# TherrmistorMux.net
KiCad netlist of a schematic drawn in Altium Designer
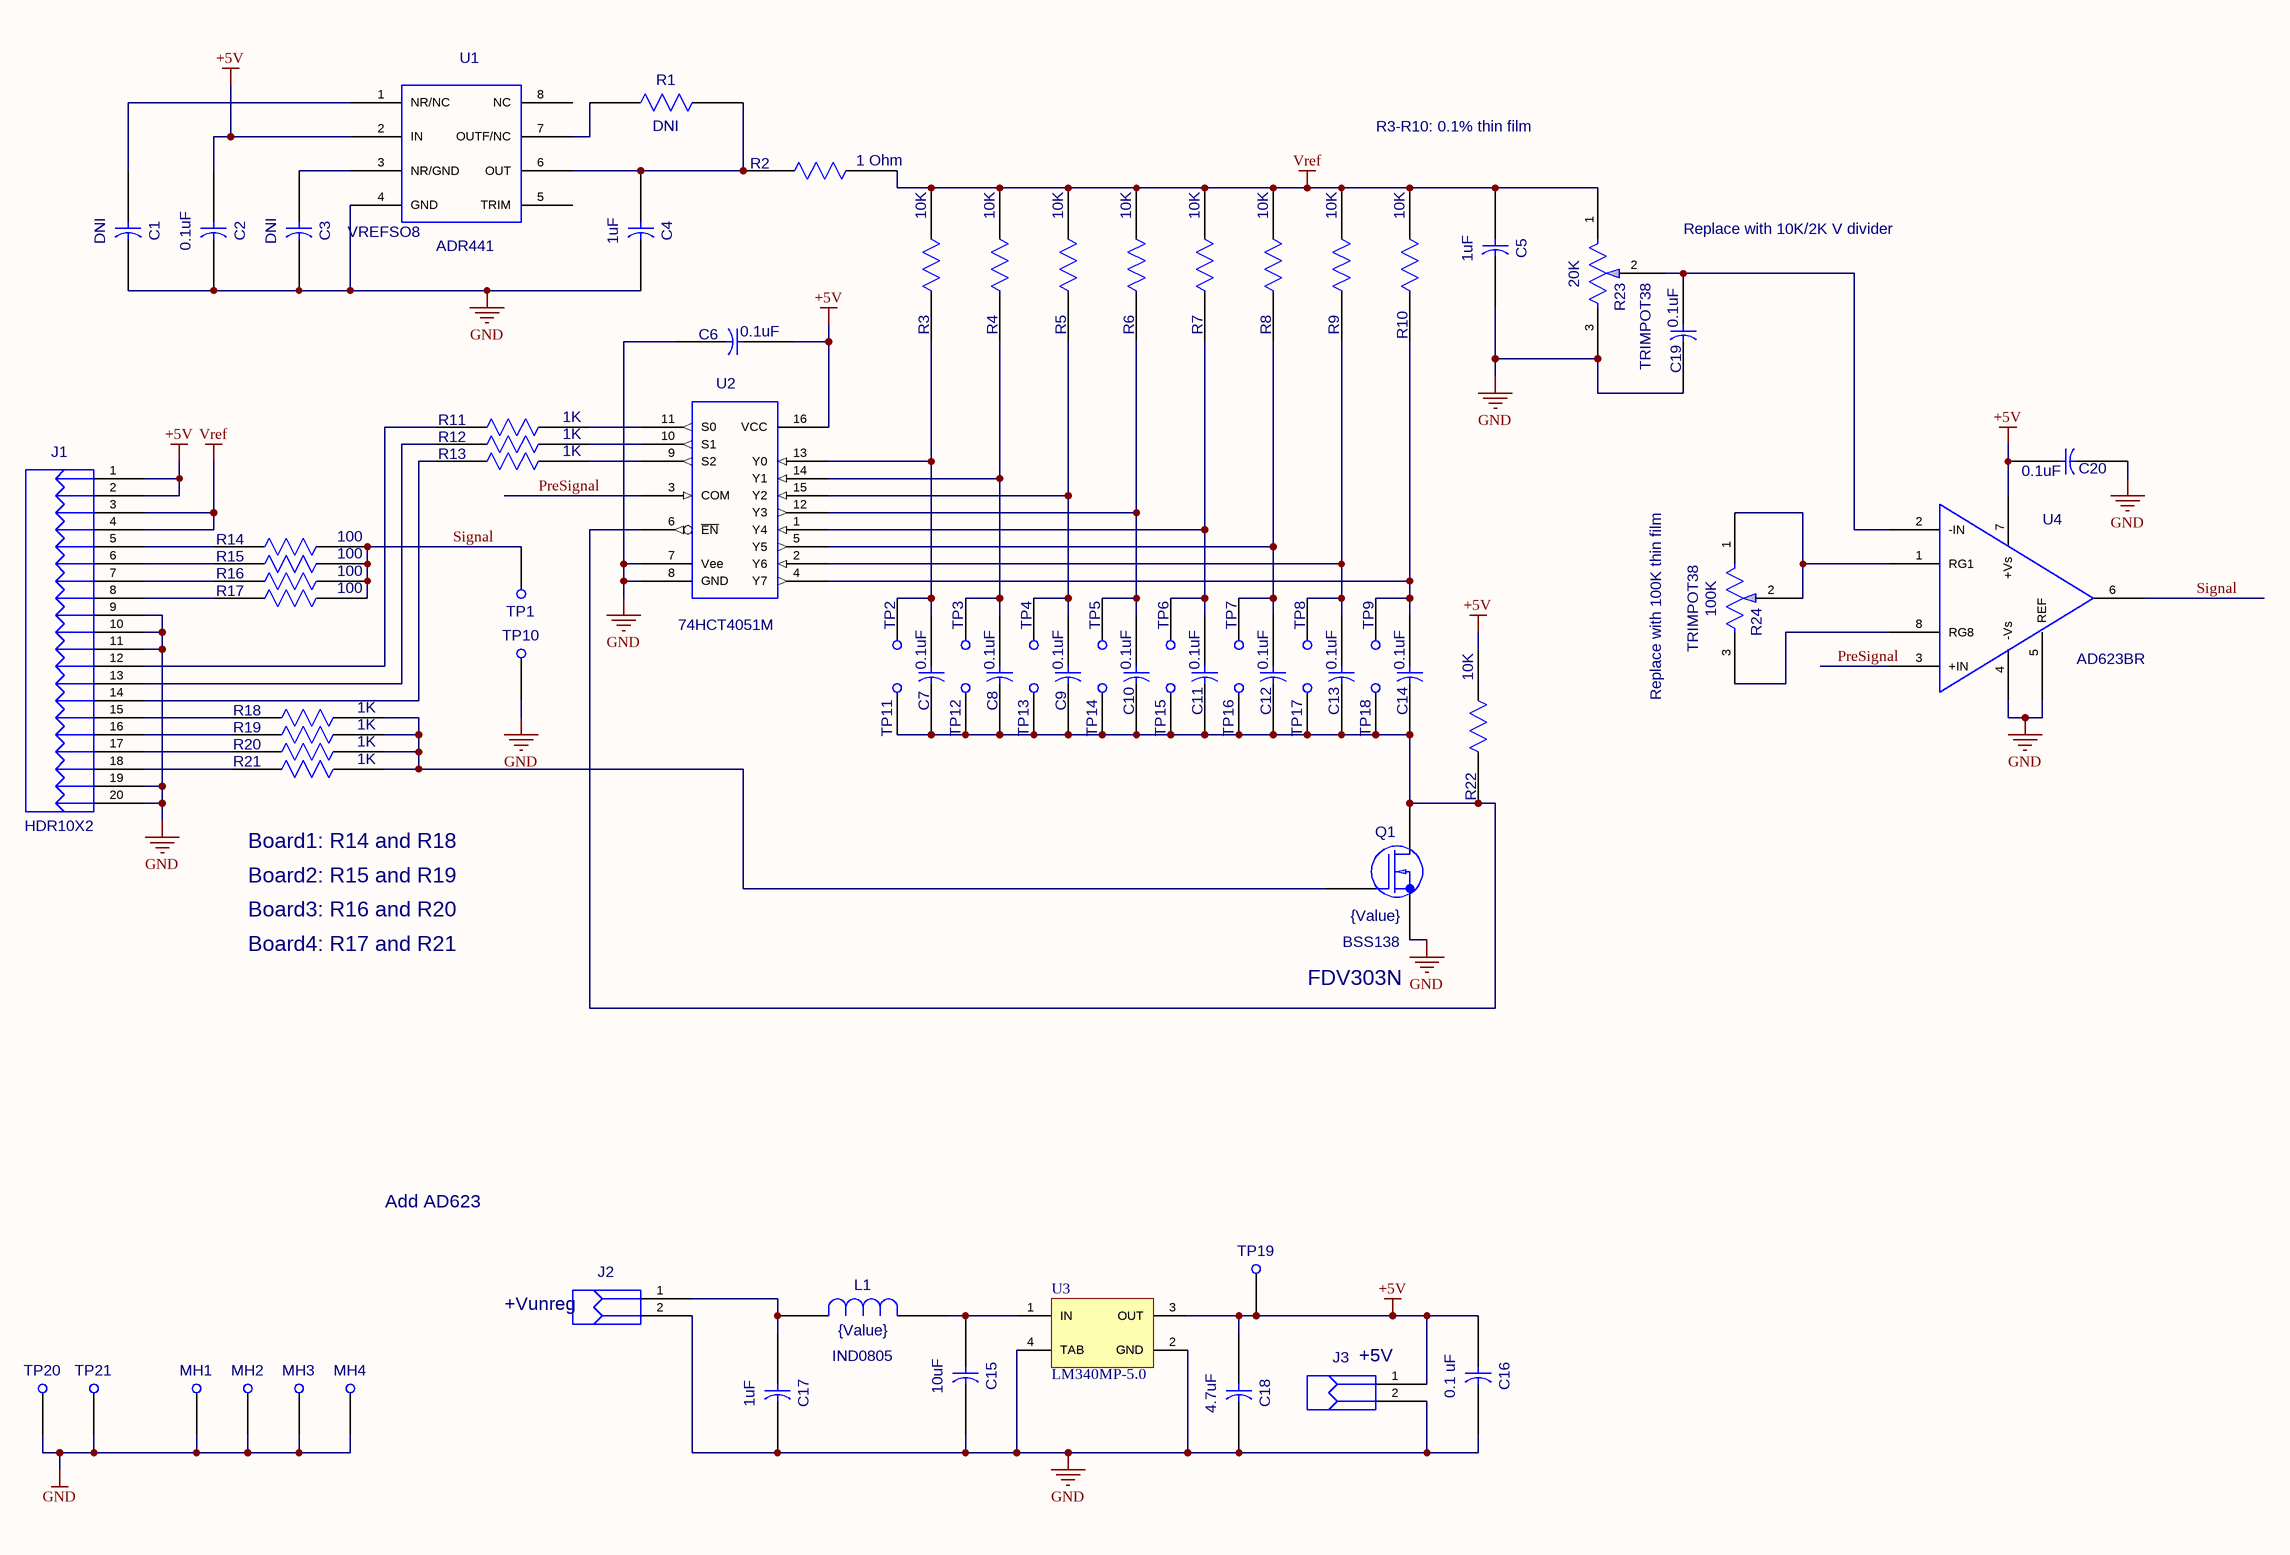
[diagram p0: TherrmistorMux.SchDoc]

(export (version "E")
  (design (tool "Eeschema 10.0.6"))
  (components
    (comp (ref "C1")
      (value "DNI")
      (footprint "RC0603")
      (description "CAP0603")
      (libsource (lib "JMAC") (part "CAP0603"))
    )
    (comp (ref "C2")
      (value "0.1uF")
      (footprint "RC0603")
      (description "CAP0603")
      (libsource (lib "JMAC") (part "CAP0603"))
    )
    (comp (ref "C3")
      (value "DNI")
      (footprint "RC0603")
      (description "CAP0603")
      (libsource (lib "JMAC") (part "CAP0603"))
    )
    (comp (ref "C4")
      (value "1uF")
      (footprint "RC0805_CAP0805(Primary)")
      (description "CAP0805")
      (libsource (lib "JMAC") (part "CAP0805"))
    )
    (comp (ref "C5")
      (value "1uF")
      (footprint "RC0805_CAP0805(Primary)")
      (description "CAP0805")
      (libsource (lib "JMAC") (part "CAP0805"))
    )
    (comp (ref "C6")
      (value "0.1uF")
      (footprint "RC0603")
      (description "CAP0603")
      (libsource (lib "JMAC") (part "CAP0603"))
    )
    (comp (ref "C7")
      (value "0.1uF")
      (footprint "RC0805_CAP0805(Primary)")
      (description "CAP0805")
      (libsource (lib "JMAC") (part "CAP0805"))
    )
    (comp (ref "C8")
      (value "0.1uF")
      (footprint "RC0805_CAP0805(Primary)")
      (description "CAP0805")
      (libsource (lib "JMAC") (part "CAP0805"))
    )
    (comp (ref "C9")
      (value "0.1uF")
      (footprint "RC0805_CAP0805(Primary)")
      (description "CAP0805")
      (libsource (lib "JMAC") (part "CAP0805"))
    )
    (comp (ref "C10")
      (value "0.1uF")
      (footprint "RC0805_CAP0805(Primary)")
      (description "CAP0805")
      (libsource (lib "JMAC") (part "CAP0805"))
    )
    (comp (ref "C11")
      (value "0.1uF")
      (footprint "RC0805_CAP0805(Primary)")
      (description "CAP0805")
      (libsource (lib "JMAC") (part "CAP0805"))
    )
    (comp (ref "C12")
      (value "0.1uF")
      (footprint "RC0805_CAP0805(Primary)")
      (description "CAP0805")
      (libsource (lib "JMAC") (part "CAP0805"))
    )
    (comp (ref "C13")
      (value "0.1uF")
      (footprint "RC0805_CAP0805(Primary)")
      (description "CAP0805")
      (libsource (lib "JMAC") (part "CAP0805"))
    )
    (comp (ref "C14")
      (value "0.1uF")
      (footprint "RC0805_CAP0805(Primary)")
      (description "CAP0805")
      (libsource (lib "JMAC") (part "CAP0805"))
    )
    (comp (ref "C15")
      (value "10uF")
      (footprint "RC1206_CAP1206(Primary)")
      (description "CAP1206")
      (libsource (lib "JMAC") (part "CAP1206"))
    )
    (comp (ref "C16")
      (value "0.1 uF")
      (footprint "RC0805_CAP0805(Primary)")
      (description "CAP0805")
      (libsource (lib "JMAC") (part "CAP0805"))
    )
    (comp (ref "C17")
      (value "1uF")
      (footprint "RC1206_CAP1206(Primary)")
      (description "CAP1206")
      (libsource (lib "JMAC") (part "CAP1206"))
    )
    (comp (ref "C18")
      (value "4.7uF")
      (footprint "RC1206_CAP1206(Primary)")
      (description "CAP1206")
      (libsource (lib "JMAC") (part "CAP1206"))
    )
    (comp (ref "C19")
      (value "0.1uF")
      (footprint "RC0603")
      (description "CAP0603")
      (libsource (lib "JMAC") (part "CAP0603"))
    )
    (comp (ref "C20")
      (value "0.1uF")
      (footprint "RC0603")
      (description "CAP0603")
      (libsource (lib "JMAC") (part "CAP0603"))
    )
    (comp (ref "J1") (value "HDR10X2") (footprint "HDR10X2") (libsource (lib "JMAC") (part "HDR10X2")))
    (comp (ref "J2")
      (value "CONN2P35MM")
      (footprint "CONN2P35MM")
      (libsource (lib "JMAC") (part "CONN2P35MM"))
    )
    (comp (ref "J3")
      (value "CONN2P35MM")
      (footprint "CONN2P35MM")
      (libsource (lib "JMAC") (part "CONN2P35MM"))
    )
    (comp (ref "L1")
      (value "IND0805")
      (footprint "RC0805_IND0805(Primary)")
      (fields (field (name "ALTIUM_VALUE") "{Value}"))
      (libsource (lib "JMAC") (part "IND0805"))
    )
    (comp (ref "MH1") (value "MH440") (footprint "M440_MH440()") (libsource (lib "*") (part "MH440")))
    (comp (ref "MH2") (value "MH440") (footprint "M440_MH440()") (libsource (lib "*") (part "MH440")))
    (comp (ref "MH3") (value "MH440") (footprint "M440_MH440()") (libsource (lib "*") (part "MH440")))
    (comp (ref "MH4") (value "MH440") (footprint "M440_MH440()") (libsource (lib "*") (part "MH440")))
    (comp (ref "Q1")
      (value "BSS138")
      (footprint "SOT-23")
      (fields (field (name "ALTIUM_VALUE") "{Value}"))
      (libsource (lib "JMAC") (part "BSS138"))
    )
    (comp (ref "R1")
      (value "DNI")
      (footprint "RC0603")
      (description "RES0603")
      (libsource (lib "JMAC") (part "RES0603"))
    )
    (comp (ref "R2")
      (value "1 Ohm")
      (footprint "RC0805_RES0805(Primary)")
      (description "RES0805")
      (libsource (lib "JMAC") (part "RES0805"))
    )
    (comp (ref "R3")
      (value "10K")
      (footprint "RC0805_RES0805(Primary)")
      (description "RES0805")
      (libsource (lib "JMAC") (part "RES0805"))
    )
    (comp (ref "R4")
      (value "10K")
      (footprint "RC0805_RES0805(Primary)")
      (description "RES0805")
      (libsource (lib "JMAC") (part "RES0805"))
    )
    (comp (ref "R5")
      (value "10K")
      (footprint "RC0805_RES0805(Primary)")
      (description "RES0805")
      (libsource (lib "JMAC") (part "RES0805"))
    )
    (comp (ref "R6")
      (value "10K")
      (footprint "RC0805_RES0805(Primary)")
      (description "RES0805")
      (libsource (lib "JMAC") (part "RES0805"))
    )
    (comp (ref "R7")
      (value "10K")
      (footprint "RC0805_RES0805(Primary)")
      (description "RES0805")
      (libsource (lib "JMAC") (part "RES0805"))
    )
    (comp (ref "R8")
      (value "10K")
      (footprint "RC0805_RES0805(Primary)")
      (description "RES0805")
      (libsource (lib "JMAC") (part "RES0805"))
    )
    (comp (ref "R9")
      (value "10K")
      (footprint "RC0805_RES0805(Primary)")
      (description "RES0805")
      (libsource (lib "JMAC") (part "RES0805"))
    )
    (comp (ref "R10")
      (value "10K")
      (footprint "RC0805_RES0805(Primary)")
      (description "RES0805")
      (libsource (lib "JMAC") (part "RES0805"))
    )
    (comp (ref "R11")
      (value "1K")
      (footprint "RC0805_RES0805(Primary)")
      (description "RES0805")
      (libsource (lib "JMAC") (part "RES0805"))
    )
    (comp (ref "R12")
      (value "1K")
      (footprint "RC0805_RES0805(Primary)")
      (description "RES0805")
      (libsource (lib "JMAC") (part "RES0805"))
    )
    (comp (ref "R13")
      (value "1K")
      (footprint "RC0805_RES0805(Primary)")
      (description "RES0805")
      (libsource (lib "JMAC") (part "RES0805"))
    )
    (comp (ref "R14")
      (value "100")
      (footprint "RC0805_RES0805(Primary)")
      (description "RES0805")
      (libsource (lib "JMAC") (part "RES0805"))
    )
    (comp (ref "R15")
      (value "100")
      (footprint "RC0805_RES0805(Primary)")
      (description "RES0805")
      (libsource (lib "JMAC") (part "RES0805"))
    )
    (comp (ref "R16")
      (value "100")
      (footprint "RC0805_RES0805(Primary)")
      (description "RES0805")
      (libsource (lib "JMAC") (part "RES0805"))
    )
    (comp (ref "R17")
      (value "100")
      (footprint "RC0805_RES0805(Primary)")
      (description "RES0805")
      (libsource (lib "JMAC") (part "RES0805"))
    )
    (comp (ref "R18")
      (value "1K")
      (footprint "RC0805_RES0805(Primary)")
      (description "RES0805")
      (libsource (lib "JMAC") (part "RES0805"))
    )
    (comp (ref "R19")
      (value "1K")
      (footprint "RC0805_RES0805(Primary)")
      (description "RES0805")
      (libsource (lib "JMAC") (part "RES0805"))
    )
    (comp (ref "R20")
      (value "1K")
      (footprint "RC0805_RES0805(Primary)")
      (description "RES0805")
      (libsource (lib "JMAC") (part "RES0805"))
    )
    (comp (ref "R21")
      (value "1K")
      (footprint "RC0805_RES0805(Primary)")
      (description "RES0805")
      (libsource (lib "JMAC") (part "RES0805"))
    )
    (comp (ref "R22")
      (value "10K")
      (footprint "RC0805_RES0805(Primary)")
      (description "RES0805")
      (libsource (lib "JMAC") (part "RES0805"))
    )
    (comp (ref "R23")
      (value "TRIMPOT38")
      (footprint "TRIM38")
      (fields (field (name "ALTIUM_VALUE") "20K"))
      (libsource (lib "JMAC") (part "TRIMPOT38"))
    )
    (comp (ref "R24")
      (value "TRIMPOT38")
      (footprint "TRIM38")
      (fields (field (name "ALTIUM_VALUE") "100K"))
      (libsource (lib "JMAC") (part "TRIMPOT38"))
    )
    (comp (ref "TP1") (value "TP38") (footprint "TP38") (libsource (lib "JMAC") (part "TP38")))
    (comp (ref "TP2") (value "TP24") (footprint "TP24") (libsource (lib "JMAC") (part "TP24")))
    (comp (ref "TP3") (value "TP24") (footprint "TP24") (libsource (lib "JMAC") (part "TP24")))
    (comp (ref "TP4") (value "TP24") (footprint "TP24") (libsource (lib "JMAC") (part "TP24")))
    (comp (ref "TP5") (value "TP24") (footprint "TP24") (libsource (lib "JMAC") (part "TP24")))
    (comp (ref "TP6") (value "TP24") (footprint "TP24") (libsource (lib "JMAC") (part "TP24")))
    (comp (ref "TP7") (value "TP24") (footprint "TP24") (libsource (lib "JMAC") (part "TP24")))
    (comp (ref "TP8") (value "TP24") (footprint "TP24") (libsource (lib "JMAC") (part "TP24")))
    (comp (ref "TP9") (value "TP24") (footprint "TP24") (libsource (lib "JMAC") (part "TP24")))
    (comp (ref "TP10") (value "TP38") (footprint "TP38") (libsource (lib "JMAC") (part "TP38")))
    (comp (ref "TP11") (value "TP24") (footprint "TP24") (libsource (lib "JMAC") (part "TP24")))
    (comp (ref "TP12") (value "TP24") (footprint "TP24") (libsource (lib "JMAC") (part "TP24")))
    (comp (ref "TP13") (value "TP24") (footprint "TP24") (libsource (lib "JMAC") (part "TP24")))
    (comp (ref "TP14") (value "TP24") (footprint "TP24") (libsource (lib "JMAC") (part "TP24")))
    (comp (ref "TP15") (value "TP24") (footprint "TP24") (libsource (lib "JMAC") (part "TP24")))
    (comp (ref "TP16") (value "TP24") (footprint "TP24") (libsource (lib "JMAC") (part "TP24")))
    (comp (ref "TP17") (value "TP24") (footprint "TP24") (libsource (lib "JMAC") (part "TP24")))
    (comp (ref "TP18") (value "TP24") (footprint "TP24") (libsource (lib "JMAC") (part "TP24")))
    (comp (ref "TP19") (value "TP52") (footprint "TP52") (libsource (lib "JMAC") (part "TP52")))
    (comp (ref "TP20") (value "TP52") (footprint "TP52") (libsource (lib "JMAC") (part "TP52")))
    (comp (ref "TP21") (value "TP52") (footprint "TP52") (libsource (lib "JMAC") (part "TP52")))
    (comp (ref "U1")
      (value "VREFSO8")
      (footprint "SO8")
      (fields (field (name "ALTIUM_VALUE") "ADR441"))
      (libsource (lib "JMAC") (part "VREFSO8"))
    )
    (comp (ref "U2") (value "74HCT4051M") (footprint "SO16") (libsource (lib "JMAC") (part "74HCT4051M")))
    (comp (ref "U3")
      (value "LM340MP-5.0")
      (footprint "MP04A_N")
      (description "Series 3-Terminal Positive Regulators")
      (fields
        (field (name "MANUFACTURER") "National Semiconductor")
        (field (name "DIGIKEYPARTNUMBER") "LM340MP-5.0CT-ND")
        (field (name "PUBLISHER") "Altium Limited")
      )
      (libsource (lib "NSC LDO") (part "LM340MP-5.0"))
    )
    (comp (ref "U4")
      (value "AD623BR")
      (footprint "SO8")
      (description "AD620BR")
      (libsource (lib "JMAC") (part "AD620BR"))
    )
  )
  (nets
    (net (code "1") (name "+5V") (class "Default")
      (node (ref "C16") (pin "A") (pinfunction "A_A") (pintype "passive"))
      (node (ref "C18") (pin "A") (pinfunction "A_A") (pintype "passive"))
      (node (ref "C2") (pin "2") (pintype "passive"))
      (node (ref "C20") (pin "2") (pintype "passive"))
      (node (ref "C6") (pin "2") (pintype "passive"))
      (node (ref "J1") (pin "1") (pinfunction "P1_1") (pintype "passive"))
      (node (ref "J1") (pin "2") (pinfunction "P2_2") (pintype "passive"))
      (node (ref "J3") (pin "1") (pintype "passive"))
      (node (ref "R22") (pin "B") (pinfunction "B_B") (pintype "passive"))
      (node (ref "TP19") (pin "1") (pintype "passive"))
      (node (ref "U1") (pin "2") (pinfunction "IN_2") (pintype "passive"))
      (node (ref "U2") (pin "16") (pinfunction "VCC_16") (pintype "power_in"))
      (node (ref "U3") (pin "3") (pinfunction "OUT_3") (pintype "power_in"))
      (node (ref "U4") (pin "7") (pinfunction "+Vs_7") (pintype "passive"))
    )
    (net (code "2") (name "/PreSignal") (class "Default")
      (node (ref "U2") (pin "3") (pinfunction "COM_3") (pintype "input"))
      (node (ref "U4") (pin "3") (pinfunction "+IN_3") (pintype "passive"))
    )
    (net (code "3") (name "/Signal") (class "Default")
      (node (ref "R14") (pin "B") (pinfunction "B_B") (pintype "passive"))
      (node (ref "R15") (pin "B") (pinfunction "B_B") (pintype "passive"))
      (node (ref "R16") (pin "B") (pinfunction "B_B") (pintype "passive"))
      (node (ref "R17") (pin "B") (pinfunction "B_B") (pintype "passive"))
      (node (ref "TP1") (pin "1") (pintype "passive"))
      (node (ref "U4") (pin "6") (pinfunction "OUT_6") (pintype "passive"))
    )
    (net (code "4") (name "GND") (class "Default")
      (node (ref "C1") (pin "1") (pintype "passive"))
      (node (ref "C15") (pin "B") (pinfunction "B_B") (pintype "passive"))
      (node (ref "C16") (pin "B") (pinfunction "B_B") (pintype "passive"))
      (node (ref "C17") (pin "B") (pinfunction "B_B") (pintype "passive"))
      (node (ref "C18") (pin "B") (pinfunction "B_B") (pintype "passive"))
      (node (ref "C19") (pin "1") (pintype "passive"))
      (node (ref "C2") (pin "1") (pintype "passive"))
      (node (ref "C20") (pin "1") (pintype "passive"))
      (node (ref "C3") (pin "1") (pintype "passive"))
      (node (ref "C4") (pin "B") (pinfunction "B_B") (pintype "passive"))
      (node (ref "C5") (pin "B") (pinfunction "B_B") (pintype "passive"))
      (node (ref "C6") (pin "1") (pintype "passive"))
      (node (ref "J1") (pin "10") (pinfunction "P10_10") (pintype "passive"))
      (node (ref "J1") (pin "11") (pinfunction "P11_11") (pintype "passive"))
      (node (ref "J1") (pin "19") (pinfunction "P19_19") (pintype "passive"))
      (node (ref "J1") (pin "20") (pinfunction "P20_20") (pintype "passive"))
      (node (ref "J1") (pin "9") (pinfunction "P9_9") (pintype "passive"))
      (node (ref "J2") (pin "2") (pintype "passive"))
      (node (ref "J3") (pin "2") (pintype "passive"))
      (node (ref "MH1") (pin "1") (pintype "passive"))
      (node (ref "MH2") (pin "1") (pintype "passive"))
      (node (ref "MH3") (pin "1") (pintype "passive"))
      (node (ref "MH4") (pin "1") (pintype "passive"))
      (node (ref "Q1") (pin "2") (pinfunction "S_2") (pintype "passive"))
      (node (ref "R23") (pin "3") (pintype "passive"))
      (node (ref "TP10") (pin "1") (pintype "passive"))
      (node (ref "TP20") (pin "1") (pintype "passive"))
      (node (ref "TP21") (pin "1") (pintype "passive"))
      (node (ref "U1") (pin "4") (pinfunction "GND_4") (pintype "passive"))
      (node (ref "U2") (pin "7") (pinfunction "Vee_7") (pintype "power_in"))
      (node (ref "U2") (pin "8") (pinfunction "GND_8") (pintype "power_in"))
      (node (ref "U3") (pin "2") (pinfunction "GND_2") (pintype "power_in"))
      (node (ref "U3") (pin "4") (pinfunction "TAB_4") (pintype "power_in"))
      (node (ref "U4") (pin "4") (pinfunction "-Vs_4") (pintype "passive"))
      (node (ref "U4") (pin "5") (pinfunction "REF_5") (pintype "passive"))
    )
    (net (code "5") (name "Net-(C17-PadA)") (class "Default")
      (node (ref "C17") (pin "A") (pinfunction "A_A") (pintype "passive"))
      (node (ref "J2") (pin "1") (pintype "passive"))
      (node (ref "L1") (pin "B") (pinfunction "B_B") (pintype "passive"))
    )
    (net (code "6") (name "Net-(J1-P5)") (class "Default")
      (node (ref "J1") (pin "5") (pinfunction "P5_5") (pintype "passive"))
      (node (ref "R14") (pin "A") (pinfunction "A_A") (pintype "passive"))
    )
    (net (code "7") (name "Net-(J1-P6)") (class "Default")
      (node (ref "J1") (pin "6") (pinfunction "P6_6") (pintype "passive"))
      (node (ref "R15") (pin "A") (pinfunction "A_A") (pintype "passive"))
    )
    (net (code "8") (name "Net-(J1-P7)") (class "Default")
      (node (ref "J1") (pin "7") (pinfunction "P7_7") (pintype "passive"))
      (node (ref "R16") (pin "A") (pinfunction "A_A") (pintype "passive"))
    )
    (net (code "9") (name "Net-(J1-P8)") (class "Default")
      (node (ref "J1") (pin "8") (pinfunction "P8_8") (pintype "passive"))
      (node (ref "R17") (pin "A") (pinfunction "A_A") (pintype "passive"))
    )
    (net (code "10") (name "Net-(J1-P12)") (class "Default")
      (node (ref "J1") (pin "12") (pinfunction "P12_12") (pintype "passive"))
      (node (ref "R11") (pin "A") (pinfunction "A_A") (pintype "passive"))
    )
    (net (code "11") (name "Net-(J1-P13)") (class "Default")
      (node (ref "J1") (pin "13") (pinfunction "P13_13") (pintype "passive"))
      (node (ref "R12") (pin "A") (pinfunction "A_A") (pintype "passive"))
    )
    (net (code "12") (name "Net-(J1-P14)") (class "Default")
      (node (ref "J1") (pin "14") (pinfunction "P14_14") (pintype "passive"))
      (node (ref "R13") (pin "A") (pinfunction "A_A") (pintype "passive"))
    )
    (net (code "13") (name "Net-(J1-P15)") (class "Default")
      (node (ref "J1") (pin "15") (pinfunction "P15_15") (pintype "passive"))
      (node (ref "R18") (pin "A") (pinfunction "A_A") (pintype "passive"))
    )
    (net (code "14") (name "Net-(J1-P16)") (class "Default")
      (node (ref "J1") (pin "16") (pinfunction "P16_16") (pintype "passive"))
      (node (ref "R19") (pin "A") (pinfunction "A_A") (pintype "passive"))
    )
    (net (code "15") (name "Net-(J1-P17)") (class "Default")
      (node (ref "J1") (pin "17") (pinfunction "P17_17") (pintype "passive"))
      (node (ref "R20") (pin "A") (pinfunction "A_A") (pintype "passive"))
    )
    (net (code "16") (name "Net-(J1-P18)") (class "Default")
      (node (ref "J1") (pin "18") (pinfunction "P18_18") (pintype "passive"))
      (node (ref "R21") (pin "A") (pinfunction "A_A") (pintype "passive"))
    )
    (net (code "17") (name "Net-(Q1-D)") (class "Default")
      (node (ref "C10") (pin "B") (pinfunction "B_B") (pintype "passive"))
      (node (ref "C11") (pin "B") (pinfunction "B_B") (pintype "passive"))
      (node (ref "C12") (pin "B") (pinfunction "B_B") (pintype "passive"))
      (node (ref "C13") (pin "B") (pinfunction "B_B") (pintype "passive"))
      (node (ref "C14") (pin "B") (pinfunction "B_B") (pintype "passive"))
      (node (ref "C7") (pin "B") (pinfunction "B_B") (pintype "passive"))
      (node (ref "C8") (pin "B") (pinfunction "B_B") (pintype "passive"))
      (node (ref "C9") (pin "B") (pinfunction "B_B") (pintype "passive"))
      (node (ref "Q1") (pin "3") (pinfunction "D_3") (pintype "passive"))
      (node (ref "R22") (pin "A") (pinfunction "A_A") (pintype "passive"))
      (node (ref "TP11") (pin "1") (pintype "passive"))
      (node (ref "TP12") (pin "1") (pintype "passive"))
      (node (ref "TP13") (pin "1") (pintype "passive"))
      (node (ref "TP14") (pin "1") (pintype "passive"))
      (node (ref "TP15") (pin "1") (pintype "passive"))
      (node (ref "TP16") (pin "1") (pintype "passive"))
      (node (ref "TP17") (pin "1") (pintype "passive"))
      (node (ref "TP18") (pin "1") (pintype "passive"))
      (node (ref "U2") (pin "6") (pinfunction "~{EN}_6") (pintype "output"))
    )
    (net (code "18") (name "Net-(Q1-G)") (class "Default")
      (node (ref "Q1") (pin "1") (pinfunction "G_1") (pintype "passive"))
      (node (ref "R18") (pin "B") (pinfunction "B_B") (pintype "passive"))
      (node (ref "R19") (pin "B") (pinfunction "B_B") (pintype "passive"))
      (node (ref "R20") (pin "B") (pinfunction "B_B") (pintype "passive"))
      (node (ref "R21") (pin "B") (pinfunction "B_B") (pintype "passive"))
    )
    (net (code "19") (name "Net-(R1-A)") (class "Default")
      (node (ref "C4") (pin "A") (pinfunction "A_A") (pintype "passive"))
      (node (ref "R1") (pin "1") (pinfunction "A_1") (pintype "passive"))
      (node (ref "R2") (pin "A") (pinfunction "A_A") (pintype "passive"))
      (node (ref "U1") (pin "6") (pinfunction "OUT_6") (pintype "passive"))
    )
    (net (code "20") (name "Net-(R1-B)") (class "Default")
      (node (ref "R1") (pin "2") (pinfunction "B_2") (pintype "passive"))
      (node (ref "U1") (pin "7") (pinfunction "OUTF/NC_7") (pintype "passive"))
    )
    (net (code "21") (name "Net-(U1-NR{slash}GND)") (class "Default")
      (node (ref "C3") (pin "2") (pintype "passive"))
      (node (ref "U1") (pin "3") (pinfunction "NR/GND_3") (pintype "passive"))
    )
    (net (code "22") (name "Net-(U1-NR{slash}NC)") (class "Default")
      (node (ref "C1") (pin "2") (pintype "passive"))
      (node (ref "U1") (pin "1") (pinfunction "NR/NC_1") (pintype "passive"))
    )
    (net (code "23") (name "Net-(U2-S0)") (class "Default")
      (node (ref "R11") (pin "B") (pinfunction "B_B") (pintype "passive"))
      (node (ref "U2") (pin "11") (pinfunction "S0_11") (pintype "output"))
    )
    (net (code "24") (name "Net-(U2-S1)") (class "Default")
      (node (ref "R12") (pin "B") (pinfunction "B_B") (pintype "passive"))
      (node (ref "U2") (pin "10") (pinfunction "S1_10") (pintype "output"))
    )
    (net (code "25") (name "Net-(U2-S2)") (class "Default")
      (node (ref "R13") (pin "B") (pinfunction "B_B") (pintype "passive"))
      (node (ref "U2") (pin "9") (pinfunction "S2_9") (pintype "output"))
    )
    (net (code "26") (name "Net-(U2-Y0)") (class "Default")
      (node (ref "C7") (pin "A") (pinfunction "A_A") (pintype "passive"))
      (node (ref "R3") (pin "A") (pinfunction "A_A") (pintype "passive"))
      (node (ref "TP2") (pin "1") (pintype "passive"))
      (node (ref "U2") (pin "13") (pinfunction "Y0_13") (pintype "input"))
    )
    (net (code "27") (name "Net-(U2-Y1)") (class "Default")
      (node (ref "C8") (pin "A") (pinfunction "A_A") (pintype "passive"))
      (node (ref "R4") (pin "A") (pinfunction "A_A") (pintype "passive"))
      (node (ref "TP3") (pin "1") (pintype "passive"))
      (node (ref "U2") (pin "14") (pinfunction "Y1_14") (pintype "input"))
    )
    (net (code "28") (name "Net-(U2-Y2)") (class "Default")
      (node (ref "C9") (pin "A") (pinfunction "A_A") (pintype "passive"))
      (node (ref "R5") (pin "A") (pinfunction "A_A") (pintype "passive"))
      (node (ref "TP4") (pin "1") (pintype "passive"))
      (node (ref "U2") (pin "15") (pinfunction "Y2_15") (pintype "input"))
    )
    (net (code "29") (name "Net-(U2-Y3)") (class "Default")
      (node (ref "C10") (pin "A") (pinfunction "A_A") (pintype "passive"))
      (node (ref "R6") (pin "A") (pinfunction "A_A") (pintype "passive"))
      (node (ref "TP5") (pin "1") (pintype "passive"))
      (node (ref "U2") (pin "12") (pinfunction "Y3_12") (pintype "output"))
    )
    (net (code "30") (name "Net-(U2-Y4)") (class "Default")
      (node (ref "C11") (pin "A") (pinfunction "A_A") (pintype "passive"))
      (node (ref "R7") (pin "A") (pinfunction "A_A") (pintype "passive"))
      (node (ref "TP6") (pin "1") (pintype "passive"))
      (node (ref "U2") (pin "1") (pinfunction "Y4_1") (pintype "input"))
    )
    (net (code "31") (name "Net-(U2-Y5)") (class "Default")
      (node (ref "C12") (pin "A") (pinfunction "A_A") (pintype "passive"))
      (node (ref "R8") (pin "A") (pinfunction "A_A") (pintype "passive"))
      (node (ref "TP7") (pin "1") (pintype "passive"))
      (node (ref "U2") (pin "5") (pinfunction "Y5_5") (pintype "output"))
    )
    (net (code "32") (name "Net-(U2-Y6)") (class "Default")
      (node (ref "C13") (pin "A") (pinfunction "A_A") (pintype "passive"))
      (node (ref "R9") (pin "A") (pinfunction "A_A") (pintype "passive"))
      (node (ref "TP8") (pin "1") (pintype "passive"))
      (node (ref "U2") (pin "2") (pinfunction "Y6_2") (pintype "input"))
    )
    (net (code "33") (name "Net-(U2-Y7)") (class "Default")
      (node (ref "C14") (pin "A") (pinfunction "A_A") (pintype "passive"))
      (node (ref "R10") (pin "A") (pinfunction "A_A") (pintype "passive"))
      (node (ref "TP9") (pin "1") (pintype "passive"))
      (node (ref "U2") (pin "4") (pinfunction "Y7_4") (pintype "output"))
    )
    (net (code "34") (name "Net-(U3-IN)") (class "Default")
      (node (ref "C15") (pin "A") (pinfunction "A_A") (pintype "passive"))
      (node (ref "L1") (pin "A") (pinfunction "A_A") (pintype "passive"))
      (node (ref "U3") (pin "1") (pinfunction "IN_1") (pintype "power_in"))
    )
    (net (code "35") (name "Net-(U4--IN)") (class "Default")
      (node (ref "C19") (pin "2") (pintype "passive"))
      (node (ref "R23") (pin "2") (pintype "passive"))
      (node (ref "U4") (pin "2") (pinfunction "-IN_2") (pintype "passive"))
    )
    (net (code "36") (name "Net-(U4-RG1)") (class "Default")
      (node (ref "R24") (pin "1") (pintype "passive"))
      (node (ref "R24") (pin "2") (pintype "passive"))
      (node (ref "U4") (pin "1") (pinfunction "RG1_1") (pintype "passive"))
    )
    (net (code "37") (name "Net-(U4-RG8)") (class "Default")
      (node (ref "R24") (pin "3") (pintype "passive"))
      (node (ref "U4") (pin "8") (pinfunction "RG8_8") (pintype "passive"))
    )
    (net (code "38") (name "Vref") (class "Default")
      (node (ref "C5") (pin "A") (pinfunction "A_A") (pintype "passive"))
      (node (ref "J1") (pin "3") (pinfunction "P3_3") (pintype "passive"))
      (node (ref "J1") (pin "4") (pinfunction "P4_4") (pintype "passive"))
      (node (ref "R10") (pin "B") (pinfunction "B_B") (pintype "passive"))
      (node (ref "R2") (pin "B") (pinfunction "B_B") (pintype "passive"))
      (node (ref "R23") (pin "1") (pintype "passive"))
      (node (ref "R3") (pin "B") (pinfunction "B_B") (pintype "passive"))
      (node (ref "R4") (pin "B") (pinfunction "B_B") (pintype "passive"))
      (node (ref "R5") (pin "B") (pinfunction "B_B") (pintype "passive"))
      (node (ref "R6") (pin "B") (pinfunction "B_B") (pintype "passive"))
      (node (ref "R7") (pin "B") (pinfunction "B_B") (pintype "passive"))
      (node (ref "R8") (pin "B") (pinfunction "B_B") (pintype "passive"))
      (node (ref "R9") (pin "B") (pinfunction "B_B") (pintype "passive"))
    )
    (net (code "39") (name "unconnected-(U1-NC-Pad8)") (class "Default")
      (node (ref "U1") (pin "8") (pinfunction "NC_8") (pintype "passive"))
    )
    (net (code "40") (name "unconnected-(U1-TRIM-Pad5)") (class "Default")
      (node (ref "U1") (pin "5") (pinfunction "TRIM_5") (pintype "passive"))
    )
  )
)
